# schem0.net
KiCad netlist of a schematic drawn in Altium Designer
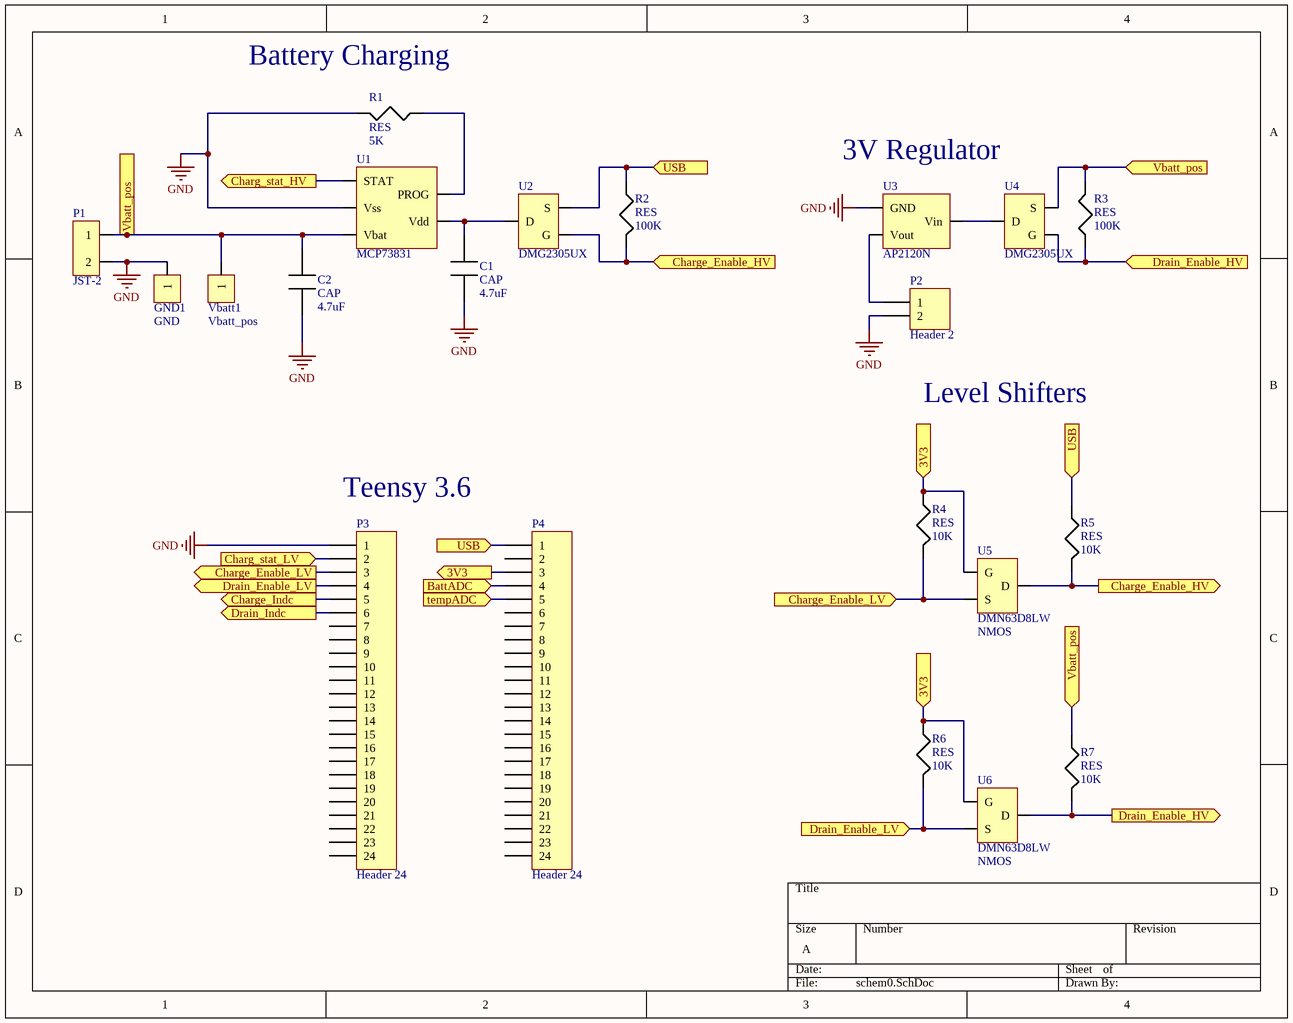
[diagram p0: schem0.SchDoc]

(export (version "E")
  (design (tool "Eeschema 10.0.6"))
  (components
    (comp (ref "C1")
      (value "CAP")
      (footprint "Cap 0603 (1608 metric)")
      (fields (field (name "ALTIUM_VALUE") "4.7uF"))
      (libsource (lib "passives") (part "CAP"))
    )
    (comp (ref "C2")
      (value "CAP")
      (footprint "Cap 0603 (1608 metric)")
      (fields (field (name "ALTIUM_VALUE") "4.7uF"))
      (libsource (lib "passives") (part "CAP"))
    )
    (comp (ref "GND1")
      (value "GND")
      (footprint "test pad")
      (description "test pad")
      (libsource (lib "test_pad") (part "test_pad"))
    )
    (comp (ref "P1") (value "JST-2") (footprint "JST-2 SMT") (libsource (lib "JST") (part "JST-2")))
    (comp (ref "P2")
      (value "Header 2")
      (footprint "HDR1X2")
      (description "Header, 2-Pin")
      (fields (field (name "PUBLISHER") "Altium Limited"))
      (libsource (lib "Miscellaneous Connectors") (part "Header 2"))
    )
    (comp (ref "P3")
      (value "Header 24")
      (footprint "HDR1X24")
      (description "Header, 24-Pin")
      (fields (field (name "PUBLISHER") "Altium Limited"))
      (libsource (lib "Miscellaneous Connectors") (part "Header 24"))
    )
    (comp (ref "P4")
      (value "Header 24")
      (footprint "HDR1X24")
      (description "Header, 24-Pin")
      (fields (field (name "PUBLISHER") "Altium Limited"))
      (libsource (lib "Miscellaneous Connectors") (part "Header 24"))
    )
    (comp (ref "R1")
      (value "RES")
      (footprint "Res 0603 (1608 metric)")
      (fields (field (name "ALTIUM_VALUE") "5K"))
      (libsource (lib "passives") (part "RES"))
    )
    (comp (ref "R2")
      (value "RES")
      (footprint "Res 0603 (1608 metric)")
      (fields (field (name "ALTIUM_VALUE") "100K"))
      (libsource (lib "passives") (part "RES"))
    )
    (comp (ref "R3")
      (value "RES")
      (footprint "Res 0603 (1608 metric)")
      (fields (field (name "ALTIUM_VALUE") "100K"))
      (libsource (lib "passives") (part "RES"))
    )
    (comp (ref "R4")
      (value "RES")
      (footprint "Res 0603 (1608 metric)")
      (fields (field (name "ALTIUM_VALUE") "10K"))
      (libsource (lib "passives") (part "RES"))
    )
    (comp (ref "R5")
      (value "RES")
      (footprint "Res 0603 (1608 metric)")
      (fields (field (name "ALTIUM_VALUE") "10K"))
      (libsource (lib "passives") (part "RES"))
    )
    (comp (ref "R6")
      (value "RES")
      (footprint "Res 0603 (1608 metric)")
      (fields (field (name "ALTIUM_VALUE") "10K"))
      (libsource (lib "passives") (part "RES"))
    )
    (comp (ref "R7")
      (value "RES")
      (footprint "Res 0603 (1608 metric)")
      (fields (field (name "ALTIUM_VALUE") "10K"))
      (libsource (lib "passives") (part "RES"))
    )
    (comp (ref "U1")
      (value "MCP73831")
      (footprint "SOT23127P600-8N")
      (description "Li-Charge Management Controllers")
      (libsource (lib "MCP73831") (part "MCP73831"))
    )
    (comp (ref "U2")
      (value "DMG2305UX")
      (footprint "SOT105P240X110-3N")
      (description "P-MOSFET")
      (libsource (lib "Diodes-Inc-FET") (part "DMG2305UX"))
    )
    (comp (ref "U3")
      (value "AP2120N")
      (footprint "AP2120")
      (description "3.0V regulator")
      (libsource (lib "Diodes-Inc-Regulator") (part "AP2120N"))
    )
    (comp (ref "U4")
      (value "DMG2305UX")
      (footprint "SOT105P240X110-3N")
      (description "P-MOSFET")
      (libsource (lib "Diodes-Inc-FET") (part "DMG2305UX"))
    )
    (comp (ref "U5")
      (value "DMN63D8LW")
      (footprint "DMN63D8LW")
      (description "N-MOSFET SOT-323")
      (fields (field (name "ALTIUM_UNNAMED_1") "NMOS"))
      (libsource (lib "Diodes-Inc-FET") (part "DMN63D8LW"))
    )
    (comp (ref "U6")
      (value "DMN63D8LW")
      (footprint "DMN63D8LW")
      (description "N-MOSFET SOT-323")
      (fields (field (name "ALTIUM_UNNAMED_1") "NMOS"))
      (libsource (lib "Diodes-Inc-FET") (part "DMN63D8LW"))
    )
    (comp (ref "Vbatt1")
      (value "Vbatt_pos")
      (footprint "test pad")
      (description "test pad")
      (libsource (lib "test_pad") (part "test_pad"))
    )
  )
  (nets
    (net (code "1") (name "/3V3") (class "Default")
      (node (ref "P4") (pin "3") (pinfunction "3_3") (pintype "passive"))
      (node (ref "R4") (pin "1") (pinfunction "1_1") (pintype "passive"))
      (node (ref "R6") (pin "1") (pinfunction "1_1") (pintype "passive"))
      (node (ref "U5") (pin "1") (pinfunction "G_1") (pintype "passive"))
      (node (ref "U6") (pin "1") (pinfunction "G_1") (pintype "passive"))
    )
    (net (code "2") (name "/BattADC") (class "Default")
      (node (ref "P4") (pin "4") (pinfunction "4_4") (pintype "passive"))
    )
    (net (code "3") (name "/Charg_stat_HV") (class "Default")
      (node (ref "U1") (pin "1") (pinfunction "STAT_1") (pintype "passive"))
    )
    (net (code "4") (name "/Charg_stat_LV") (class "Default")
      (node (ref "P3") (pin "2") (pinfunction "2_2") (pintype "passive"))
    )
    (net (code "5") (name "/Charge_Enable_HV") (class "Default")
      (node (ref "R2") (pin "2") (pinfunction "2_2") (pintype "passive"))
      (node (ref "R5") (pin "2") (pinfunction "2_2") (pintype "passive"))
      (node (ref "U2") (pin "1") (pinfunction "G_1") (pintype "passive"))
      (node (ref "U5") (pin "3") (pinfunction "D_3") (pintype "passive"))
    )
    (net (code "6") (name "/Charge_Enable_LV") (class "Default")
      (node (ref "P3") (pin "3") (pinfunction "3_3") (pintype "passive"))
      (node (ref "R4") (pin "2") (pinfunction "2_2") (pintype "passive"))
      (node (ref "U5") (pin "2") (pinfunction "S_2") (pintype "passive"))
    )
    (net (code "7") (name "/Charge_Indc") (class "Default")
      (node (ref "P3") (pin "5") (pinfunction "5_5") (pintype "passive"))
    )
    (net (code "8") (name "/Drain_Enable_HV") (class "Default")
      (node (ref "R3") (pin "1") (pinfunction "1_1") (pintype "passive"))
      (node (ref "R7") (pin "2") (pinfunction "2_2") (pintype "passive"))
      (node (ref "U4") (pin "1") (pinfunction "G_1") (pintype "passive"))
      (node (ref "U6") (pin "3") (pinfunction "D_3") (pintype "passive"))
    )
    (net (code "9") (name "/Drain_Enable_LV") (class "Default")
      (node (ref "P3") (pin "4") (pinfunction "4_4") (pintype "passive"))
      (node (ref "R6") (pin "2") (pinfunction "2_2") (pintype "passive"))
      (node (ref "U6") (pin "2") (pinfunction "S_2") (pintype "passive"))
    )
    (net (code "10") (name "/Drain_Indc") (class "Default")
      (node (ref "P3") (pin "6") (pinfunction "6_6") (pintype "passive"))
    )
    (net (code "11") (name "/USB") (class "Default")
      (node (ref "P4") (pin "1") (pinfunction "1_1") (pintype "passive"))
      (node (ref "R2") (pin "1") (pinfunction "1_1") (pintype "passive"))
      (node (ref "R5") (pin "1") (pinfunction "1_1") (pintype "passive"))
      (node (ref "U2") (pin "2") (pinfunction "S_2") (pintype "passive"))
    )
    (net (code "12") (name "/Vbatt_pos") (class "Default")
      (node (ref "C2") (pin "2") (pinfunction "2_2") (pintype "passive"))
      (node (ref "P1") (pin "1") (pinfunction "1_1") (pintype "passive"))
      (node (ref "R3") (pin "2") (pinfunction "2_2") (pintype "passive"))
      (node (ref "R7") (pin "1") (pinfunction "1_1") (pintype "passive"))
      (node (ref "U1") (pin "3") (pinfunction "Vbat_3") (pintype "passive"))
      (node (ref "U4") (pin "2") (pinfunction "S_2") (pintype "passive"))
      (node (ref "Vbatt1") (pin "1") (pinfunction "1_1") (pintype "passive"))
    )
    (net (code "13") (name "/tempADC") (class "Default")
      (node (ref "P4") (pin "5") (pinfunction "5_5") (pintype "passive"))
    )
    (net (code "14") (name "GND") (class "Default")
      (node (ref "C1") (pin "1") (pinfunction "1_1") (pintype "passive"))
      (node (ref "C2") (pin "1") (pinfunction "1_1") (pintype "passive"))
      (node (ref "GND1") (pin "1") (pinfunction "1_1") (pintype "passive"))
      (node (ref "P1") (pin "2") (pinfunction "2_2") (pintype "passive"))
      (node (ref "P2") (pin "2") (pinfunction "2_2") (pintype "passive"))
      (node (ref "P3") (pin "1") (pinfunction "1_1") (pintype "passive"))
      (node (ref "R1") (pin "2") (pinfunction "2_2") (pintype "passive"))
      (node (ref "U1") (pin "2") (pinfunction "Vss_2") (pintype "passive"))
      (node (ref "U3") (pin "1") (pinfunction "GND_1") (pintype "passive"))
    )
    (net (code "15") (name "Net-(U1-PROG)") (class "Default")
      (node (ref "R1") (pin "1") (pinfunction "1_1") (pintype "passive"))
      (node (ref "U1") (pin "5") (pinfunction "PROG_5") (pintype "passive"))
    )
    (net (code "16") (name "Net-(U1-Vdd)") (class "Default")
      (node (ref "C1") (pin "2") (pinfunction "2_2") (pintype "passive"))
      (node (ref "U1") (pin "4") (pinfunction "Vdd_4") (pintype "passive"))
      (node (ref "U2") (pin "3") (pinfunction "D_3") (pintype "passive"))
    )
    (net (code "17") (name "Net-(U3-Vin)") (class "Default")
      (node (ref "U3") (pin "3") (pinfunction "Vin_3") (pintype "passive"))
      (node (ref "U4") (pin "3") (pinfunction "D_3") (pintype "passive"))
    )
    (net (code "18") (name "Net-(U3-Vout)") (class "Default")
      (node (ref "P2") (pin "1") (pinfunction "1_1") (pintype "passive"))
      (node (ref "U3") (pin "2") (pinfunction "Vout_2") (pintype "passive"))
    )
    (net (code "19") (name "unconnected-(P3-Pad7)") (class "Default")
      (node (ref "P3") (pin "7") (pinfunction "7_7") (pintype "passive"))
    )
    (net (code "20") (name "unconnected-(P3-Pad8)") (class "Default")
      (node (ref "P3") (pin "8") (pinfunction "8_8") (pintype "passive"))
    )
    (net (code "21") (name "unconnected-(P3-Pad9)") (class "Default")
      (node (ref "P3") (pin "9") (pinfunction "9_9") (pintype "passive"))
    )
    (net (code "22") (name "unconnected-(P3-Pad10)") (class "Default")
      (node (ref "P3") (pin "10") (pinfunction "10_10") (pintype "passive"))
    )
    (net (code "23") (name "unconnected-(P3-Pad11)") (class "Default")
      (node (ref "P3") (pin "11") (pinfunction "11_11") (pintype "passive"))
    )
    (net (code "24") (name "unconnected-(P3-Pad12)") (class "Default")
      (node (ref "P3") (pin "12") (pinfunction "12_12") (pintype "passive"))
    )
    (net (code "25") (name "unconnected-(P3-Pad13)") (class "Default")
      (node (ref "P3") (pin "13") (pinfunction "13_13") (pintype "passive"))
    )
    (net (code "26") (name "unconnected-(P3-Pad14)") (class "Default")
      (node (ref "P3") (pin "14") (pinfunction "14_14") (pintype "passive"))
    )
    (net (code "27") (name "unconnected-(P3-Pad15)") (class "Default")
      (node (ref "P3") (pin "15") (pinfunction "15_15") (pintype "passive"))
    )
    (net (code "28") (name "unconnected-(P3-Pad16)") (class "Default")
      (node (ref "P3") (pin "16") (pinfunction "16_16") (pintype "passive"))
    )
    (net (code "29") (name "unconnected-(P3-Pad17)") (class "Default")
      (node (ref "P3") (pin "17") (pinfunction "17_17") (pintype "passive"))
    )
    (net (code "30") (name "unconnected-(P3-Pad18)") (class "Default")
      (node (ref "P3") (pin "18") (pinfunction "18_18") (pintype "passive"))
    )
    (net (code "31") (name "unconnected-(P3-Pad19)") (class "Default")
      (node (ref "P3") (pin "19") (pinfunction "19_19") (pintype "passive"))
    )
    (net (code "32") (name "unconnected-(P3-Pad20)") (class "Default")
      (node (ref "P3") (pin "20") (pinfunction "20_20") (pintype "passive"))
    )
    (net (code "33") (name "unconnected-(P3-Pad21)") (class "Default")
      (node (ref "P3") (pin "21") (pinfunction "21_21") (pintype "passive"))
    )
    (net (code "34") (name "unconnected-(P3-Pad22)") (class "Default")
      (node (ref "P3") (pin "22") (pinfunction "22_22") (pintype "passive"))
    )
    (net (code "35") (name "unconnected-(P3-Pad23)") (class "Default")
      (node (ref "P3") (pin "23") (pinfunction "23_23") (pintype "passive"))
    )
    (net (code "36") (name "unconnected-(P3-Pad24)") (class "Default")
      (node (ref "P3") (pin "24") (pinfunction "24_24") (pintype "passive"))
    )
    (net (code "37") (name "unconnected-(P4-Pad2)") (class "Default")
      (node (ref "P4") (pin "2") (pinfunction "2_2") (pintype "passive"))
    )
    (net (code "38") (name "unconnected-(P4-Pad6)") (class "Default")
      (node (ref "P4") (pin "6") (pinfunction "6_6") (pintype "passive"))
    )
    (net (code "39") (name "unconnected-(P4-Pad7)") (class "Default")
      (node (ref "P4") (pin "7") (pinfunction "7_7") (pintype "passive"))
    )
    (net (code "40") (name "unconnected-(P4-Pad8)") (class "Default")
      (node (ref "P4") (pin "8") (pinfunction "8_8") (pintype "passive"))
    )
    (net (code "41") (name "unconnected-(P4-Pad9)") (class "Default")
      (node (ref "P4") (pin "9") (pinfunction "9_9") (pintype "passive"))
    )
    (net (code "42") (name "unconnected-(P4-Pad10)") (class "Default")
      (node (ref "P4") (pin "10") (pinfunction "10_10") (pintype "passive"))
    )
    (net (code "43") (name "unconnected-(P4-Pad11)") (class "Default")
      (node (ref "P4") (pin "11") (pinfunction "11_11") (pintype "passive"))
    )
    (net (code "44") (name "unconnected-(P4-Pad12)") (class "Default")
      (node (ref "P4") (pin "12") (pinfunction "12_12") (pintype "passive"))
    )
    (net (code "45") (name "unconnected-(P4-Pad13)") (class "Default")
      (node (ref "P4") (pin "13") (pinfunction "13_13") (pintype "passive"))
    )
    (net (code "46") (name "unconnected-(P4-Pad14)") (class "Default")
      (node (ref "P4") (pin "14") (pinfunction "14_14") (pintype "passive"))
    )
    (net (code "47") (name "unconnected-(P4-Pad15)") (class "Default")
      (node (ref "P4") (pin "15") (pinfunction "15_15") (pintype "passive"))
    )
    (net (code "48") (name "unconnected-(P4-Pad16)") (class "Default")
      (node (ref "P4") (pin "16") (pinfunction "16_16") (pintype "passive"))
    )
    (net (code "49") (name "unconnected-(P4-Pad17)") (class "Default")
      (node (ref "P4") (pin "17") (pinfunction "17_17") (pintype "passive"))
    )
    (net (code "50") (name "unconnected-(P4-Pad18)") (class "Default")
      (node (ref "P4") (pin "18") (pinfunction "18_18") (pintype "passive"))
    )
    (net (code "51") (name "unconnected-(P4-Pad19)") (class "Default")
      (node (ref "P4") (pin "19") (pinfunction "19_19") (pintype "passive"))
    )
    (net (code "52") (name "unconnected-(P4-Pad20)") (class "Default")
      (node (ref "P4") (pin "20") (pinfunction "20_20") (pintype "passive"))
    )
    (net (code "53") (name "unconnected-(P4-Pad21)") (class "Default")
      (node (ref "P4") (pin "21") (pinfunction "21_21") (pintype "passive"))
    )
    (net (code "54") (name "unconnected-(P4-Pad22)") (class "Default")
      (node (ref "P4") (pin "22") (pinfunction "22_22") (pintype "passive"))
    )
    (net (code "55") (name "unconnected-(P4-Pad23)") (class "Default")
      (node (ref "P4") (pin "23") (pinfunction "23_23") (pintype "passive"))
    )
    (net (code "56") (name "unconnected-(P4-Pad24)") (class "Default")
      (node (ref "P4") (pin "24") (pinfunction "24_24") (pintype "passive"))
    )
  )
)
